# Qwiic_GPS_-_Ublox_SAM-M8Q.net
KiCad netlist of a schematic drawn in EAGLE
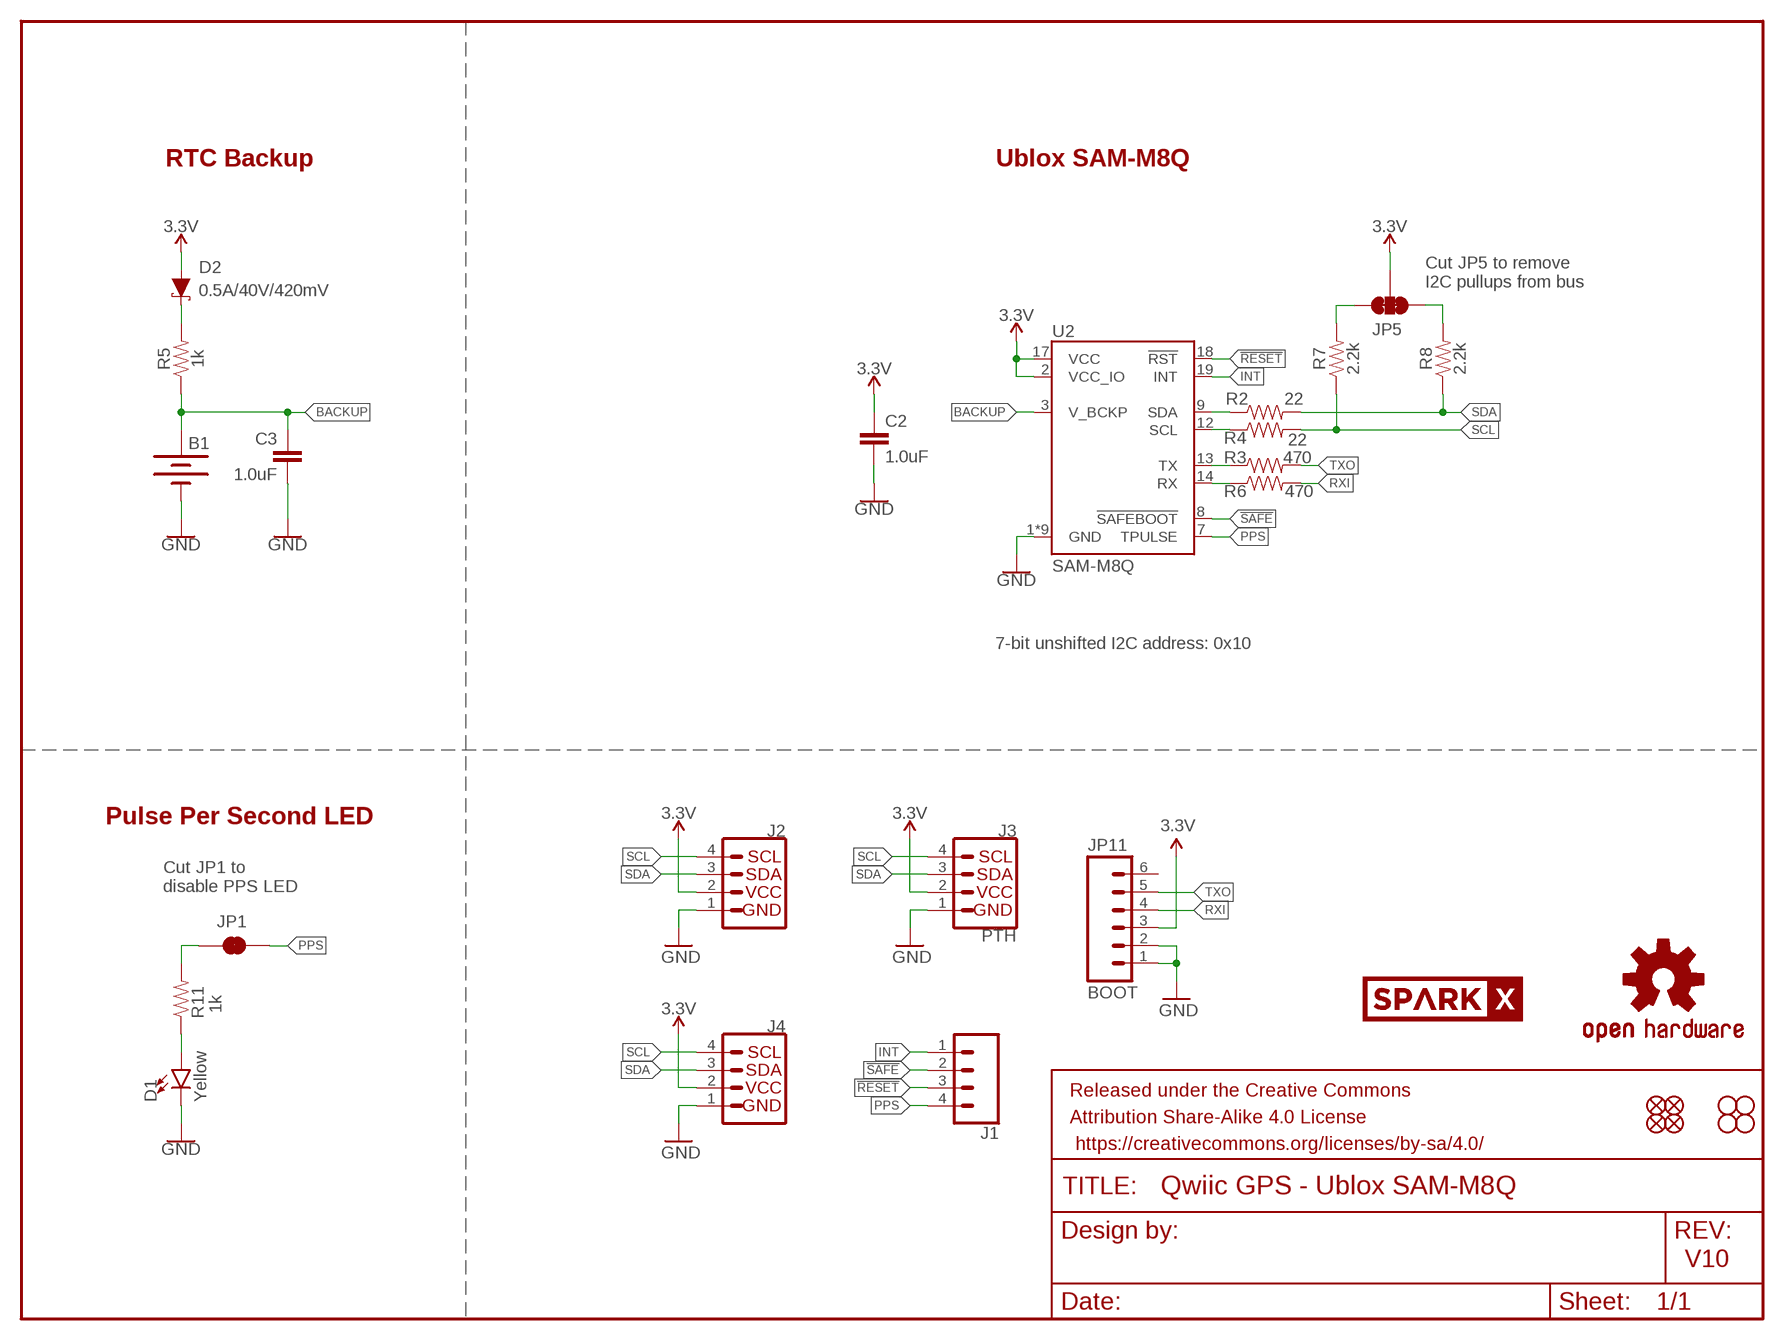
[diagram p0: schematic, sheet 1]

(export (version "E")
  (design (tool "Eeschema 10.0.6"))
  (components
    (comp (ref "B1")
      (value "6.8MM_COIN_CELL")
      (footprint "eagle-import:ML414H_IV01E")
      (libsource (lib "eagle-import") (part "ML414H_IV01E_BATTERY"))
    )
    (comp (ref "C2")
      (value "1.0uF")
      (footprint "eagle-import:0603")
      (libsource (lib "eagle-import") (part "1.0UF-0603-16V-10%"))
    )
    (comp (ref "C3")
      (value "1.0uF")
      (footprint "eagle-import:0603")
      (libsource (lib "eagle-import") (part "1.0UF-0603-16V-10%"))
    )
    (comp (ref "D1")
      (value "Yellow")
      (footprint "eagle-import:LED-0603")
      (libsource (lib "eagle-import") (part "LED-YELLOW0603"))
    )
    (comp (ref "D2")
      (value "0.5A/40V/420mV")
      (footprint "eagle-import:SOD-323")
      (libsource (lib "eagle-import") (part "DIODE-SCHOTTKY-PMEG4005EJ"))
    )
    (comp (ref "FRAME1")
      (value "FRAME-LETTER")
      (footprint "eagle-import:CREATIVE_COMMONS")
      (libsource (lib "eagle-import") (part "FRAME-LETTER"))
    )
    (comp (ref "J1")
      (value "CONN_041X04_NO_SILK")
      (footprint "eagle-import:1X04_NO_SILK")
      (libsource (lib "eagle-import") (part "CONN_041X04_NO_SILK"))
    )
    (comp (ref "J2")
      (value "I2C_STANDARDQWIIC")
      (footprint "eagle-import:1X04_1MM_RA")
      (libsource (lib "eagle-import") (part "I2C_STANDARDQWIIC"))
    )
    (comp (ref "J3")
      (value "PTH")
      (footprint "eagle-import:1X04_NO_SILK")
      (libsource (lib "eagle-import") (part "SparkX_I2C_STANDARD_NO_SILK"))
    )
    (comp (ref "J4")
      (value "I2C_STANDARDQWIIC")
      (footprint "eagle-import:1X04_1MM_RA")
      (libsource (lib "eagle-import") (part "I2C_STANDARDQWIIC"))
    )
    (comp (ref "JP1")
      (value "JUMPER-SMT_2_NC_TRACE_SILK")
      (footprint "eagle-import:SMT-JUMPER_2_NC_TRACE_SILK")
      (libsource (lib "eagle-import") (part "JUMPER-SMT_2_NC_TRACE_SILK"))
    )
    (comp (ref "JP2")
      (value "FIDUCIALUFIDUCIAL")
      (footprint "eagle-import:MICRO-FIDUCIAL")
      (libsource (lib "eagle-import") (part "FIDUCIALUFIDUCIAL"))
    )
    (comp (ref "JP3")
      (value "STAND-OFF")
      (footprint "eagle-import:STAND-OFF")
      (libsource (lib "eagle-import") (part "STAND-OFF"))
    )
    (comp (ref "JP4")
      (value "STAND-OFF")
      (footprint "eagle-import:STAND-OFF")
      (libsource (lib "eagle-import") (part "STAND-OFF"))
    )
    (comp (ref "JP5")
      (value "JUMPER-SMT_3_2-NC_TRACE_SILK")
      (footprint "eagle-import:SMT-JUMPER_3_2-NC_TRACE_SILK")
      (libsource (lib "eagle-import") (part "JUMPER-SMT_3_2-NC_TRACE_SILK"))
    )
    (comp (ref "JP6")
      (value "FIDUCIALUFIDUCIAL")
      (footprint "eagle-import:MICRO-FIDUCIAL")
      (libsource (lib "eagle-import") (part "FIDUCIALUFIDUCIAL"))
    )
    (comp (ref "JP7")
      (value "FIDUCIALUFIDUCIAL")
      (footprint "eagle-import:MICRO-FIDUCIAL")
      (libsource (lib "eagle-import") (part "FIDUCIALUFIDUCIAL"))
    )
    (comp (ref "JP8")
      (value "FIDUCIALUFIDUCIAL")
      (footprint "eagle-import:MICRO-FIDUCIAL")
      (libsource (lib "eagle-import") (part "FIDUCIALUFIDUCIAL"))
    )
    (comp (ref "JP9")
      (value "STAND-OFF")
      (footprint "eagle-import:STAND-OFF")
      (libsource (lib "eagle-import") (part "STAND-OFF"))
    )
    (comp (ref "JP10")
      (value "STAND-OFF")
      (footprint "eagle-import:STAND-OFF")
      (libsource (lib "eagle-import") (part "STAND-OFF"))
    )
    (comp (ref "JP11")
      (value "BOOT")
      (footprint "eagle-import:1X06_NO_SILK")
      (libsource (lib "eagle-import") (part "M06NO_SILK_FEMALE_PTH"))
    )
    (comp (ref "LOGO1")
      (value "OSHW-LOGOMINI")
      (footprint "eagle-import:OSHW-LOGO-MINI")
      (libsource (lib "eagle-import") (part "OSHW-LOGOMINI"))
    )
    (comp (ref "R2")
      (value "22")
      (footprint "eagle-import:0603")
      (libsource (lib "eagle-import") (part "22OHM-0603-1/10W-1%"))
    )
    (comp (ref "R3")
      (value "470")
      (footprint "eagle-import:0603")
      (libsource (lib "eagle-import") (part "470OHM-0603-1/10W-1%"))
    )
    (comp (ref "R4")
      (value "22")
      (footprint "eagle-import:0603")
      (libsource (lib "eagle-import") (part "22OHM-0603-1/10W-1%"))
    )
    (comp (ref "R5")
      (value "1k")
      (footprint "eagle-import:0603")
      (libsource (lib "eagle-import") (part "1KOHM-0603-1/10W-1%"))
    )
    (comp (ref "R6")
      (value "470")
      (footprint "eagle-import:0603")
      (libsource (lib "eagle-import") (part "470OHM-0603-1/10W-1%"))
    )
    (comp (ref "R7")
      (value "2.2k")
      (footprint "eagle-import:0603")
      (libsource (lib "eagle-import") (part "2.2KOHM-0603-1/10W-1%"))
    )
    (comp (ref "R8")
      (value "2.2k")
      (footprint "eagle-import:0603")
      (libsource (lib "eagle-import") (part "2.2KOHM-0603-1/10W-1%"))
    )
    (comp (ref "R11")
      (value "1k")
      (footprint "eagle-import:0603")
      (libsource (lib "eagle-import") (part "1KOHM-0603-1/10W-1%"))
    )
    (comp (ref "U$31")
      (value "SPARKX-LOGO4")
      (footprint "eagle-import:SPARKX-MEDIUM")
      (libsource (lib "eagle-import") (part "SPARKX-LOGO4"))
    )
    (comp (ref "U2")
      (value "SAM-M8Q")
      (footprint "eagle-import:SAM-M8Q")
      (libsource (lib "eagle-import") (part "SAM-M8Q"))
    )
  )
  (nets
    (net (code "1") (name "/~{RESET}") (class "Default")
      (node (ref "J1") (pin "3") (pinfunction "3_3") (pintype "passive"))
      (node (ref "U2") (pin "18") (pinfunction "~{RST}_18") (pintype "bidirectional"))
    )
    (net (code "2") (name "/~{SAFE}") (class "Default")
      (node (ref "J1") (pin "2") (pinfunction "2_2") (pintype "passive"))
      (node (ref "U2") (pin "8") (pinfunction "~{SAFEBOOT}_8") (pintype "bidirectional"))
    )
    (net (code "3") (name "3.3V") (class "Default")
      (node (ref "C2") (pin "1") (pinfunction "1_1") (pintype "passive"))
      (node (ref "D2") (pin "A") (pinfunction "A_A") (pintype "passive"))
      (node (ref "J2") (pin "2") (pinfunction "2_2") (pintype "power_in"))
      (node (ref "J3") (pin "2") (pinfunction "VCC_2") (pintype "power_in"))
      (node (ref "J4") (pin "2") (pinfunction "2_2") (pintype "power_in"))
      (node (ref "JP11") (pin "3") (pinfunction "3_3") (pintype "passive"))
      (node (ref "JP5") (pin "2") (pinfunction "2_2") (pintype "passive"))
      (node (ref "U2") (pin "17") (pinfunction "VCC_17") (pintype "bidirectional"))
      (node (ref "U2") (pin "2") (pinfunction "VCC_IO_2") (pintype "bidirectional"))
    )
    (net (code "4") (name "BACKUP") (class "Default")
      (node (ref "B1") (pin "+") (pinfunction "+_+") (pintype "power_in"))
      (node (ref "C3") (pin "1") (pinfunction "1_1") (pintype "passive"))
      (node (ref "R5") (pin "1") (pinfunction "1_1") (pintype "passive"))
      (node (ref "U2") (pin "3") (pinfunction "V_BCKP_3") (pintype "bidirectional"))
    )
    (net (code "5") (name "GND") (class "Default")
      (node (ref "B1") (pin "-") (pinfunction "-_-") (pintype "power_in"))
      (node (ref "C2") (pin "2") (pinfunction "2_2") (pintype "passive"))
      (node (ref "C3") (pin "2") (pinfunction "2_2") (pintype "passive"))
      (node (ref "D1") (pin "C") (pinfunction "C_C") (pintype "passive"))
      (node (ref "J2") (pin "1") (pinfunction "1_1") (pintype "power_in"))
      (node (ref "J3") (pin "1") (pinfunction "GND_1") (pintype "power_in"))
      (node (ref "J4") (pin "1") (pinfunction "1_1") (pintype "power_in"))
      (node (ref "JP11") (pin "1") (pinfunction "1_1") (pintype "passive"))
      (node (ref "JP11") (pin "2") (pinfunction "2_2") (pintype "passive"))
      (node (ref "U2") (pin "1") (pinfunction "GND_1") (pintype "bidirectional"))
      (node (ref "U2") (pin "10") (pinfunction "GND_10") (pintype "bidirectional"))
      (node (ref "U2") (pin "11") (pinfunction "GND_11") (pintype "bidirectional"))
      (node (ref "U2") (pin "15") (pinfunction "GND_15") (pintype "bidirectional"))
      (node (ref "U2") (pin "16") (pinfunction "GND_16") (pintype "bidirectional"))
      (node (ref "U2") (pin "20") (pinfunction "GND_20") (pintype "bidirectional"))
      (node (ref "U2") (pin "4") (pinfunction "GND_4") (pintype "bidirectional"))
      (node (ref "U2") (pin "5") (pinfunction "GND_5") (pintype "bidirectional"))
      (node (ref "U2") (pin "6") (pinfunction "GND_6") (pintype "bidirectional"))
    )
    (net (code "6") (name "INT") (class "Default")
      (node (ref "J1") (pin "1") (pinfunction "1_1") (pintype "passive"))
      (node (ref "U2") (pin "19") (pinfunction "INT_19") (pintype "bidirectional"))
    )
    (net (code "7") (name "Net-(D1-PadA)") (class "Default")
      (node (ref "D1") (pin "A") (pinfunction "A_A") (pintype "passive"))
      (node (ref "R11") (pin "1") (pinfunction "1_1") (pintype "passive"))
    )
    (net (code "8") (name "Net-(D2-PadC)") (class "Default")
      (node (ref "D2") (pin "C") (pinfunction "C_C") (pintype "passive"))
      (node (ref "R5") (pin "2") (pinfunction "2_2") (pintype "passive"))
    )
    (net (code "9") (name "Net-(JP1-Pad1)") (class "Default")
      (node (ref "JP1") (pin "1") (pinfunction "1_1") (pintype "passive"))
      (node (ref "R11") (pin "2") (pinfunction "2_2") (pintype "passive"))
    )
    (net (code "10") (name "Net-(JP5-Pad1)") (class "Default")
      (node (ref "JP5") (pin "1") (pinfunction "1_1") (pintype "passive"))
      (node (ref "R8") (pin "2") (pinfunction "2_2") (pintype "passive"))
    )
    (net (code "11") (name "Net-(JP5-Pad3)") (class "Default")
      (node (ref "JP5") (pin "3") (pinfunction "3_3") (pintype "passive"))
      (node (ref "R7") (pin "2") (pinfunction "2_2") (pintype "passive"))
    )
    (net (code "12") (name "Net-(U2-RX)") (class "Default")
      (node (ref "R6") (pin "1") (pinfunction "1_1") (pintype "passive"))
      (node (ref "U2") (pin "14") (pinfunction "RX_14") (pintype "bidirectional"))
    )
    (net (code "13") (name "Net-(U2-SCL)") (class "Default")
      (node (ref "R4") (pin "1") (pinfunction "1_1") (pintype "passive"))
      (node (ref "U2") (pin "12") (pinfunction "SCL_12") (pintype "bidirectional"))
    )
    (net (code "14") (name "Net-(U2-SDA)") (class "Default")
      (node (ref "R2") (pin "1") (pinfunction "1_1") (pintype "passive"))
      (node (ref "U2") (pin "9") (pinfunction "SDA_9") (pintype "bidirectional"))
    )
    (net (code "15") (name "Net-(U2-TX)") (class "Default")
      (node (ref "R3") (pin "1") (pinfunction "1_1") (pintype "passive"))
      (node (ref "U2") (pin "13") (pinfunction "TX_13") (pintype "bidirectional"))
    )
    (net (code "16") (name "PPS") (class "Default")
      (node (ref "J1") (pin "4") (pinfunction "4_4") (pintype "passive"))
      (node (ref "JP1") (pin "2") (pinfunction "2_2") (pintype "passive"))
      (node (ref "U2") (pin "7") (pinfunction "TPULSE_7") (pintype "bidirectional"))
    )
    (net (code "17") (name "RXI") (class "Default")
      (node (ref "JP11") (pin "4") (pinfunction "4_4") (pintype "passive"))
      (node (ref "R6") (pin "2") (pinfunction "2_2") (pintype "passive"))
    )
    (net (code "18") (name "SCL") (class "Default")
      (node (ref "J2") (pin "4") (pinfunction "4_4") (pintype "passive"))
      (node (ref "J3") (pin "4") (pinfunction "SCL_4") (pintype "passive"))
      (node (ref "J4") (pin "4") (pinfunction "4_4") (pintype "passive"))
      (node (ref "R4") (pin "2") (pinfunction "2_2") (pintype "passive"))
      (node (ref "R7") (pin "1") (pinfunction "1_1") (pintype "passive"))
    )
    (net (code "19") (name "SDA") (class "Default")
      (node (ref "J2") (pin "3") (pinfunction "3_3") (pintype "passive"))
      (node (ref "J3") (pin "3") (pinfunction "SDA_3") (pintype "passive"))
      (node (ref "J4") (pin "3") (pinfunction "3_3") (pintype "passive"))
      (node (ref "R2") (pin "2") (pinfunction "2_2") (pintype "passive"))
      (node (ref "R8") (pin "1") (pinfunction "1_1") (pintype "passive"))
    )
    (net (code "20") (name "TXO") (class "Default")
      (node (ref "JP11") (pin "5") (pinfunction "5_5") (pintype "passive"))
      (node (ref "R3") (pin "2") (pinfunction "2_2") (pintype "passive"))
    )
    (net (code "21") (name "unconnected-(JP11-Pad6)") (class "Default")
      (node (ref "JP11") (pin "6") (pinfunction "6_6") (pintype "passive"))
    )
  )
)
